# irboard.net
KiCad netlist of a schematic drawn in EAGLE
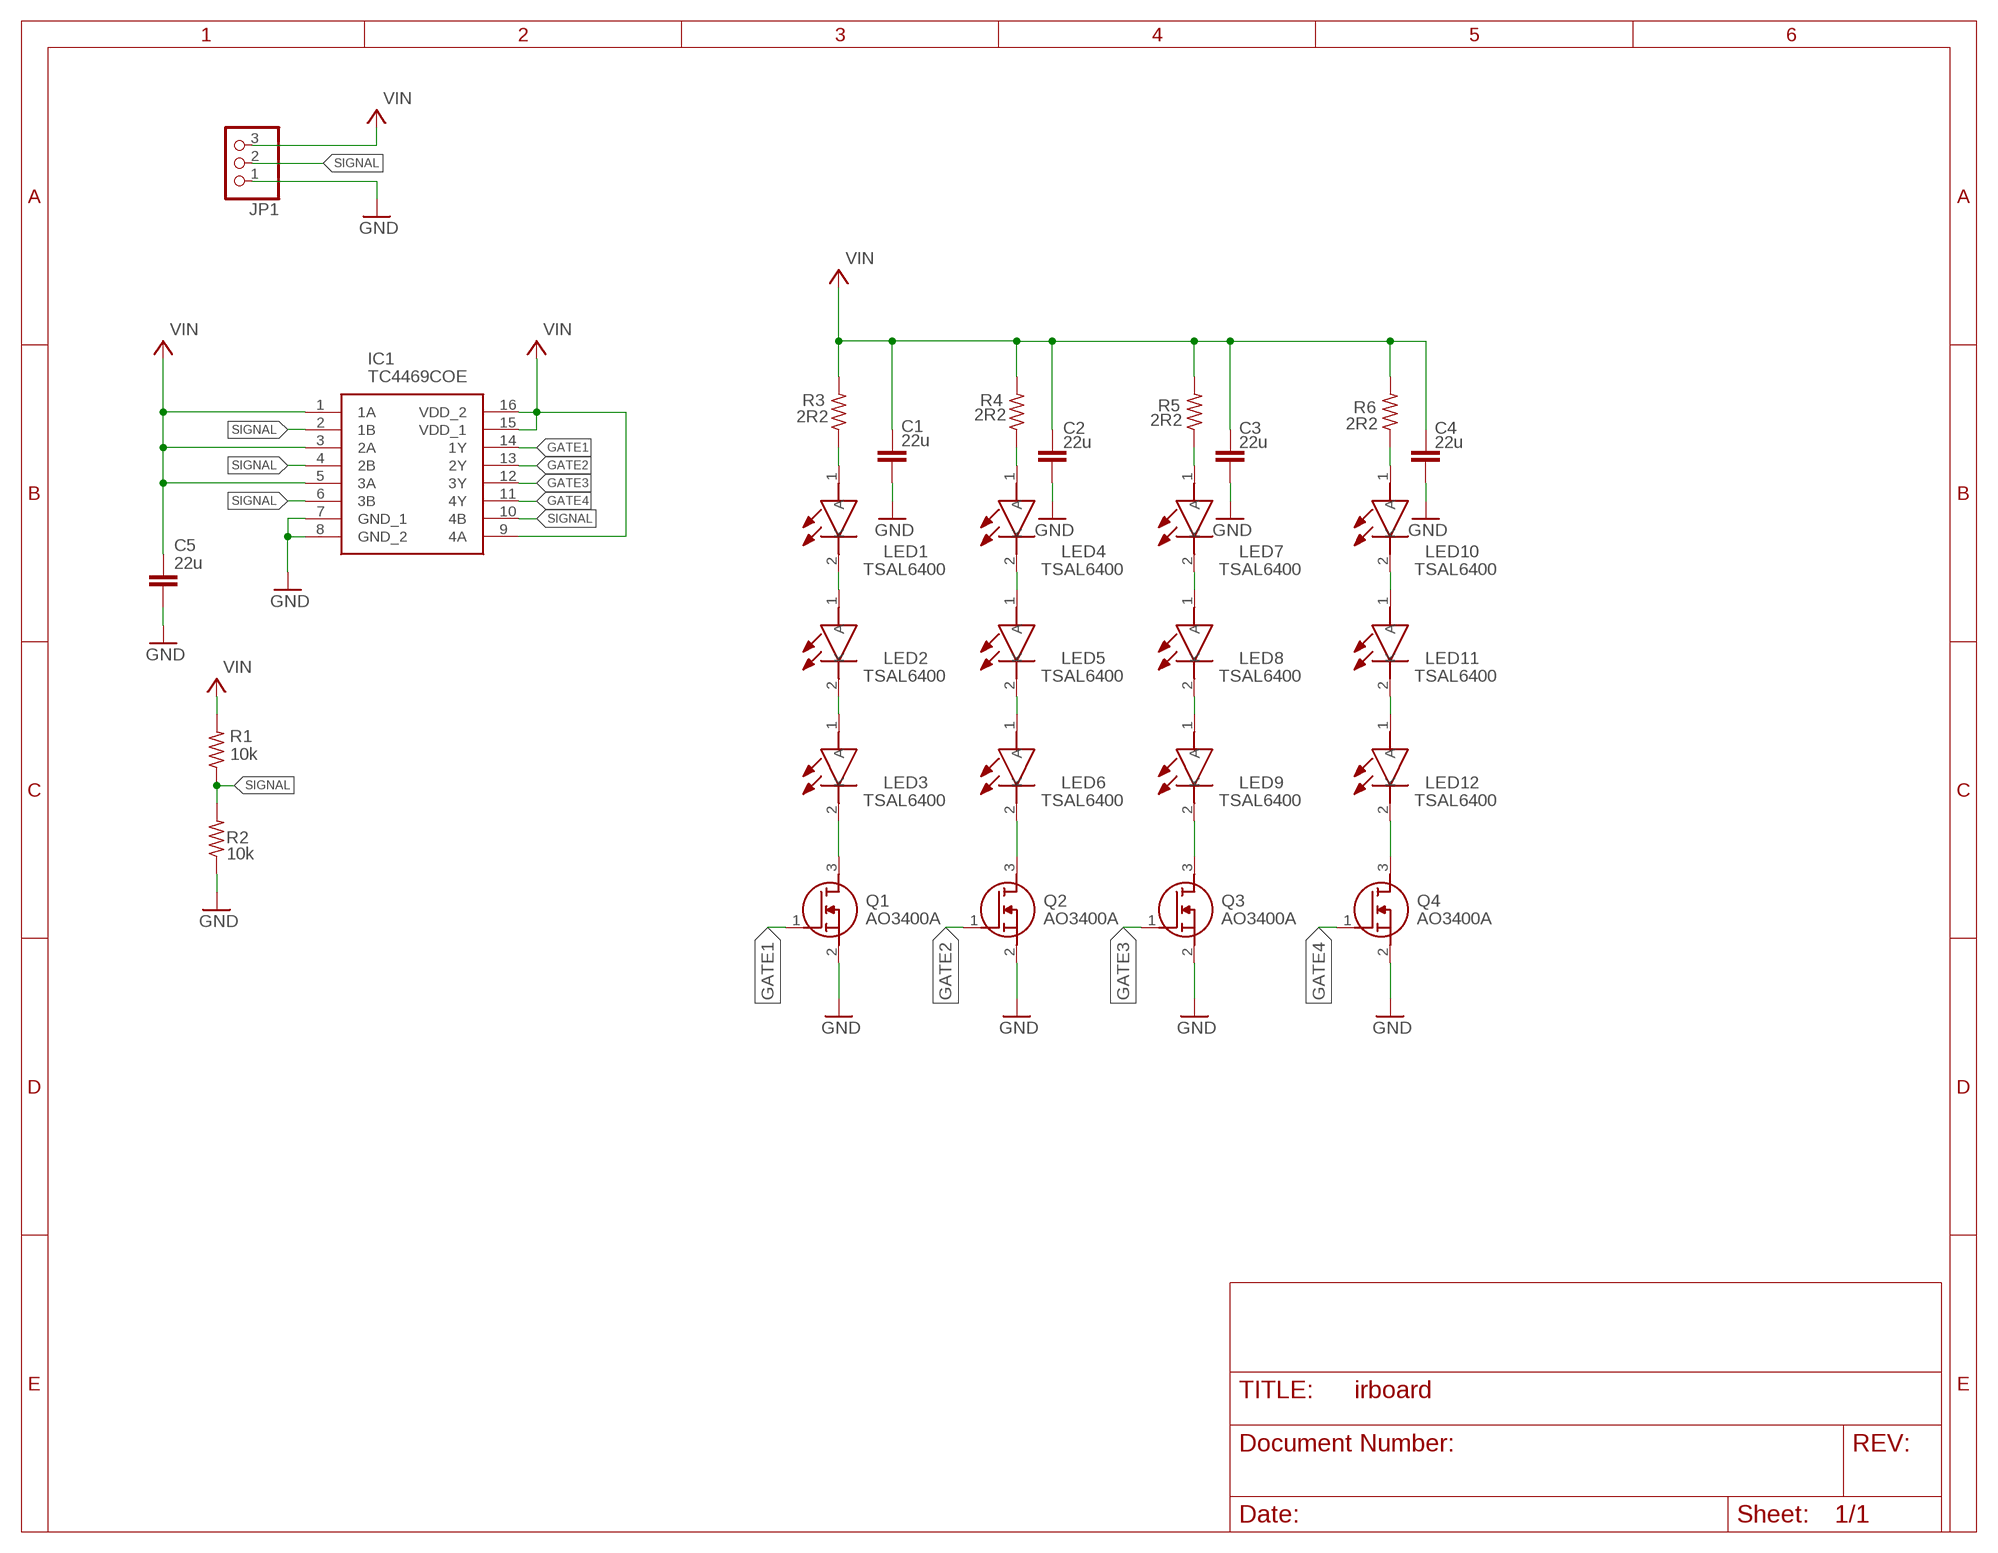
[diagram p0: schematic, sheet 1]

(export (version "E")
  (design (tool "Eeschema 10.0.6"))
  (components
    (comp (ref "C1")
      (value "22u")
      (footprint "eagle-import:C0805")
      (libsource (lib "eagle-import") (part "CAP_SMD0805"))
    )
    (comp (ref "C2")
      (value "22u")
      (footprint "eagle-import:C0805")
      (libsource (lib "eagle-import") (part "CAP_SMD0805"))
    )
    (comp (ref "C3")
      (value "22u")
      (footprint "eagle-import:C0805")
      (libsource (lib "eagle-import") (part "CAP_SMD0805"))
    )
    (comp (ref "C4")
      (value "22u")
      (footprint "eagle-import:C0805")
      (libsource (lib "eagle-import") (part "CAP_SMD0805"))
    )
    (comp (ref "C5")
      (value "22u")
      (footprint "eagle-import:C0805")
      (libsource (lib "eagle-import") (part "CAP_SMD0805"))
    )
    (comp (ref "IC1")
      (value "TC4469COE")
      (footprint "eagle-import:SOIC127P1034X264-16N")
      (fields (field (name "MOUSER_PART_NUMBER") "579-TC4469COE") (field (name "RS_PART_NUMBER") "6684411P"))
      (libsource (lib "eagle-import") (part "TC4469COE"))
    )
    (comp (ref "JP1")
      (value "PINHD-1X3")
      (footprint "eagle-import:1X03")
      (libsource (lib "eagle-import") (part "PINHD-1X3"))
    )
    (comp (ref "LED1")
      (value "TSAL6400")
      (footprint "eagle-import:TSAL6100")
      (fields (field (name "MOUSER_PART_NUMBER") "782-TSAL6400") (field (name "RS_PART_NUMBER") "8187672"))
      (libsource (lib "eagle-import") (part "TSAL6400"))
    )
    (comp (ref "LED2")
      (value "TSAL6400")
      (footprint "eagle-import:TSAL6100")
      (fields (field (name "MOUSER_PART_NUMBER") "782-TSAL6400") (field (name "RS_PART_NUMBER") "8187672"))
      (libsource (lib "eagle-import") (part "TSAL6400"))
    )
    (comp (ref "LED3")
      (value "TSAL6400")
      (footprint "eagle-import:TSAL6100")
      (fields (field (name "MOUSER_PART_NUMBER") "782-TSAL6400") (field (name "RS_PART_NUMBER") "8187672"))
      (libsource (lib "eagle-import") (part "TSAL6400"))
    )
    (comp (ref "LED4")
      (value "TSAL6400")
      (footprint "eagle-import:TSAL6100")
      (fields (field (name "MOUSER_PART_NUMBER") "782-TSAL6400") (field (name "RS_PART_NUMBER") "8187672"))
      (libsource (lib "eagle-import") (part "TSAL6400"))
    )
    (comp (ref "LED5")
      (value "TSAL6400")
      (footprint "eagle-import:TSAL6100")
      (fields (field (name "MOUSER_PART_NUMBER") "782-TSAL6400") (field (name "RS_PART_NUMBER") "8187672"))
      (libsource (lib "eagle-import") (part "TSAL6400"))
    )
    (comp (ref "LED6")
      (value "TSAL6400")
      (footprint "eagle-import:TSAL6100")
      (fields (field (name "MOUSER_PART_NUMBER") "782-TSAL6400") (field (name "RS_PART_NUMBER") "8187672"))
      (libsource (lib "eagle-import") (part "TSAL6400"))
    )
    (comp (ref "LED7")
      (value "TSAL6400")
      (footprint "eagle-import:TSAL6100")
      (fields (field (name "MOUSER_PART_NUMBER") "782-TSAL6400") (field (name "RS_PART_NUMBER") "8187672"))
      (libsource (lib "eagle-import") (part "TSAL6400"))
    )
    (comp (ref "LED8")
      (value "TSAL6400")
      (footprint "eagle-import:TSAL6100")
      (fields (field (name "MOUSER_PART_NUMBER") "782-TSAL6400") (field (name "RS_PART_NUMBER") "8187672"))
      (libsource (lib "eagle-import") (part "TSAL6400"))
    )
    (comp (ref "LED9")
      (value "TSAL6400")
      (footprint "eagle-import:TSAL6100")
      (fields (field (name "MOUSER_PART_NUMBER") "782-TSAL6400") (field (name "RS_PART_NUMBER") "8187672"))
      (libsource (lib "eagle-import") (part "TSAL6400"))
    )
    (comp (ref "LED10")
      (value "TSAL6400")
      (footprint "eagle-import:TSAL6100")
      (fields (field (name "MOUSER_PART_NUMBER") "782-TSAL6400") (field (name "RS_PART_NUMBER") "8187672"))
      (libsource (lib "eagle-import") (part "TSAL6400"))
    )
    (comp (ref "LED11")
      (value "TSAL6400")
      (footprint "eagle-import:TSAL6100")
      (fields (field (name "MOUSER_PART_NUMBER") "782-TSAL6400") (field (name "RS_PART_NUMBER") "8187672"))
      (libsource (lib "eagle-import") (part "TSAL6400"))
    )
    (comp (ref "LED12")
      (value "TSAL6400")
      (footprint "eagle-import:TSAL6100")
      (fields (field (name "MOUSER_PART_NUMBER") "782-TSAL6400") (field (name "RS_PART_NUMBER") "8187672"))
      (libsource (lib "eagle-import") (part "TSAL6400"))
    )
    (comp (ref "Q1")
      (value "AO3400A")
      (footprint "eagle-import:SOT95P280X125-3N")
      (libsource (lib "eagle-import") (part "AO3400A"))
    )
    (comp (ref "Q2")
      (value "AO3400A")
      (footprint "eagle-import:SOT95P280X125-3N")
      (libsource (lib "eagle-import") (part "AO3400A"))
    )
    (comp (ref "Q3")
      (value "AO3400A")
      (footprint "eagle-import:SOT95P280X125-3N")
      (libsource (lib "eagle-import") (part "AO3400A"))
    )
    (comp (ref "Q4")
      (value "AO3400A")
      (footprint "eagle-import:SOT95P280X125-3N")
      (libsource (lib "eagle-import") (part "AO3400A"))
    )
    (comp (ref "R1")
      (value "10k")
      (footprint "eagle-import:R0603")
      (libsource (lib "eagle-import") (part "RES_SMD0603"))
    )
    (comp (ref "R2")
      (value "10k")
      (footprint "eagle-import:R0603")
      (libsource (lib "eagle-import") (part "RES_SMD0603"))
    )
    (comp (ref "R3")
      (value "2R2")
      (footprint "eagle-import:R0603")
      (libsource (lib "eagle-import") (part "RES_SMD0603"))
    )
    (comp (ref "R4")
      (value "2R2")
      (footprint "eagle-import:R0603")
      (libsource (lib "eagle-import") (part "RES_SMD0603"))
    )
    (comp (ref "R5")
      (value "2R2")
      (footprint "eagle-import:R0603")
      (libsource (lib "eagle-import") (part "RES_SMD0603"))
    )
    (comp (ref "R6")
      (value "2R2")
      (footprint "eagle-import:R0603")
      (libsource (lib "eagle-import") (part "RES_SMD0603"))
    )
  )
  (nets
    (net (code "1") (name "GATE1") (class "Default")
      (node (ref "IC1") (pin "14") (pinfunction "1Y_14") (pintype "bidirectional"))
      (node (ref "Q1") (pin "1") (pinfunction "G_1") (pintype "bidirectional"))
    )
    (net (code "2") (name "GATE2") (class "Default")
      (node (ref "IC1") (pin "13") (pinfunction "2Y_13") (pintype "bidirectional"))
      (node (ref "Q2") (pin "1") (pinfunction "G_1") (pintype "bidirectional"))
    )
    (net (code "3") (name "GATE3") (class "Default")
      (node (ref "IC1") (pin "12") (pinfunction "3Y_12") (pintype "bidirectional"))
      (node (ref "Q3") (pin "1") (pinfunction "G_1") (pintype "bidirectional"))
    )
    (net (code "4") (name "GATE4") (class "Default")
      (node (ref "IC1") (pin "11") (pinfunction "4Y_11") (pintype "bidirectional"))
      (node (ref "Q4") (pin "1") (pinfunction "G_1") (pintype "bidirectional"))
    )
    (net (code "5") (name "GND") (class "Default")
      (node (ref "C1") (pin "2") (pinfunction "2_2") (pintype "passive"))
      (node (ref "C2") (pin "2") (pinfunction "2_2") (pintype "passive"))
      (node (ref "C3") (pin "2") (pinfunction "2_2") (pintype "passive"))
      (node (ref "C4") (pin "2") (pinfunction "2_2") (pintype "passive"))
      (node (ref "C5") (pin "2") (pinfunction "2_2") (pintype "passive"))
      (node (ref "IC1") (pin "7") (pinfunction "GND_1_7") (pintype "bidirectional"))
      (node (ref "IC1") (pin "8") (pinfunction "GND_2_8") (pintype "bidirectional"))
      (node (ref "JP1") (pin "1") (pinfunction "1_1") (pintype "passive"))
      (node (ref "Q1") (pin "2") (pinfunction "S_2") (pintype "bidirectional"))
      (node (ref "Q2") (pin "2") (pinfunction "S_2") (pintype "bidirectional"))
      (node (ref "Q3") (pin "2") (pinfunction "S_2") (pintype "bidirectional"))
      (node (ref "Q4") (pin "2") (pinfunction "S_2") (pintype "bidirectional"))
      (node (ref "R2") (pin "1") (pinfunction "1_1") (pintype "passive"))
    )
    (net (code "6") (name "Net-(LED1-A)") (class "Default")
      (node (ref "LED1") (pin "1") (pinfunction "A_1") (pintype "bidirectional"))
      (node (ref "R3") (pin "1") (pinfunction "1_1") (pintype "passive"))
    )
    (net (code "7") (name "Net-(LED1-K)") (class "Default")
      (node (ref "LED1") (pin "2") (pinfunction "K_2") (pintype "bidirectional"))
      (node (ref "LED2") (pin "1") (pinfunction "A_1") (pintype "bidirectional"))
    )
    (net (code "8") (name "Net-(LED2-K)") (class "Default")
      (node (ref "LED2") (pin "2") (pinfunction "K_2") (pintype "bidirectional"))
      (node (ref "LED3") (pin "1") (pinfunction "A_1") (pintype "bidirectional"))
    )
    (net (code "9") (name "Net-(LED3-K)") (class "Default")
      (node (ref "LED3") (pin "2") (pinfunction "K_2") (pintype "bidirectional"))
      (node (ref "Q1") (pin "3") (pinfunction "D_3") (pintype "bidirectional"))
    )
    (net (code "10") (name "Net-(LED4-A)") (class "Default")
      (node (ref "LED4") (pin "1") (pinfunction "A_1") (pintype "bidirectional"))
      (node (ref "R4") (pin "1") (pinfunction "1_1") (pintype "passive"))
    )
    (net (code "11") (name "Net-(LED4-K)") (class "Default")
      (node (ref "LED4") (pin "2") (pinfunction "K_2") (pintype "bidirectional"))
      (node (ref "LED5") (pin "1") (pinfunction "A_1") (pintype "bidirectional"))
    )
    (net (code "12") (name "Net-(LED5-K)") (class "Default")
      (node (ref "LED5") (pin "2") (pinfunction "K_2") (pintype "bidirectional"))
      (node (ref "LED6") (pin "1") (pinfunction "A_1") (pintype "bidirectional"))
    )
    (net (code "13") (name "Net-(LED6-K)") (class "Default")
      (node (ref "LED6") (pin "2") (pinfunction "K_2") (pintype "bidirectional"))
      (node (ref "Q2") (pin "3") (pinfunction "D_3") (pintype "bidirectional"))
    )
    (net (code "14") (name "Net-(LED7-A)") (class "Default")
      (node (ref "LED7") (pin "1") (pinfunction "A_1") (pintype "bidirectional"))
      (node (ref "R5") (pin "1") (pinfunction "1_1") (pintype "passive"))
    )
    (net (code "15") (name "Net-(LED7-K)") (class "Default")
      (node (ref "LED7") (pin "2") (pinfunction "K_2") (pintype "bidirectional"))
      (node (ref "LED8") (pin "1") (pinfunction "A_1") (pintype "bidirectional"))
    )
    (net (code "16") (name "Net-(LED8-K)") (class "Default")
      (node (ref "LED8") (pin "2") (pinfunction "K_2") (pintype "bidirectional"))
      (node (ref "LED9") (pin "1") (pinfunction "A_1") (pintype "bidirectional"))
    )
    (net (code "17") (name "Net-(LED9-K)") (class "Default")
      (node (ref "LED9") (pin "2") (pinfunction "K_2") (pintype "bidirectional"))
      (node (ref "Q3") (pin "3") (pinfunction "D_3") (pintype "bidirectional"))
    )
    (net (code "18") (name "Net-(LED10-A)") (class "Default")
      (node (ref "LED10") (pin "1") (pinfunction "A_1") (pintype "bidirectional"))
      (node (ref "R6") (pin "1") (pinfunction "1_1") (pintype "passive"))
    )
    (net (code "19") (name "Net-(LED10-K)") (class "Default")
      (node (ref "LED10") (pin "2") (pinfunction "K_2") (pintype "bidirectional"))
      (node (ref "LED11") (pin "1") (pinfunction "A_1") (pintype "bidirectional"))
    )
    (net (code "20") (name "Net-(LED11-K)") (class "Default")
      (node (ref "LED11") (pin "2") (pinfunction "K_2") (pintype "bidirectional"))
      (node (ref "LED12") (pin "1") (pinfunction "A_1") (pintype "bidirectional"))
    )
    (net (code "21") (name "Net-(LED12-K)") (class "Default")
      (node (ref "LED12") (pin "2") (pinfunction "K_2") (pintype "bidirectional"))
      (node (ref "Q4") (pin "3") (pinfunction "D_3") (pintype "bidirectional"))
    )
    (net (code "22") (name "SIGNAL") (class "Default")
      (node (ref "IC1") (pin "10") (pinfunction "4B_10") (pintype "bidirectional"))
      (node (ref "IC1") (pin "2") (pinfunction "1B_2") (pintype "bidirectional"))
      (node (ref "IC1") (pin "4") (pinfunction "2B_4") (pintype "bidirectional"))
      (node (ref "IC1") (pin "6") (pinfunction "3B_6") (pintype "bidirectional"))
      (node (ref "JP1") (pin "2") (pinfunction "2_2") (pintype "passive"))
      (node (ref "R1") (pin "1") (pinfunction "1_1") (pintype "passive"))
      (node (ref "R2") (pin "2") (pinfunction "2_2") (pintype "passive"))
    )
    (net (code "23") (name "VIN") (class "Default")
      (node (ref "C1") (pin "1") (pinfunction "1_1") (pintype "passive"))
      (node (ref "C2") (pin "1") (pinfunction "1_1") (pintype "passive"))
      (node (ref "C3") (pin "1") (pinfunction "1_1") (pintype "passive"))
      (node (ref "C4") (pin "1") (pinfunction "1_1") (pintype "passive"))
      (node (ref "C5") (pin "1") (pinfunction "1_1") (pintype "passive"))
      (node (ref "IC1") (pin "1") (pinfunction "1A_1") (pintype "bidirectional"))
      (node (ref "IC1") (pin "15") (pinfunction "VDD_1_15") (pintype "bidirectional"))
      (node (ref "IC1") (pin "16") (pinfunction "VDD_2_16") (pintype "bidirectional"))
      (node (ref "IC1") (pin "3") (pinfunction "2A_3") (pintype "bidirectional"))
      (node (ref "IC1") (pin "5") (pinfunction "3A_5") (pintype "bidirectional"))
      (node (ref "IC1") (pin "9") (pinfunction "4A_9") (pintype "bidirectional"))
      (node (ref "JP1") (pin "3") (pinfunction "3_3") (pintype "passive"))
      (node (ref "R1") (pin "2") (pinfunction "2_2") (pintype "passive"))
      (node (ref "R3") (pin "2") (pinfunction "2_2") (pintype "passive"))
      (node (ref "R4") (pin "2") (pinfunction "2_2") (pintype "passive"))
      (node (ref "R5") (pin "2") (pinfunction "2_2") (pintype "passive"))
      (node (ref "R6") (pin "2") (pinfunction "2_2") (pintype "passive"))
    )
  )
)
